# 3Dheater2.net
KiCad netlist of a schematic drawn in Altium Designer
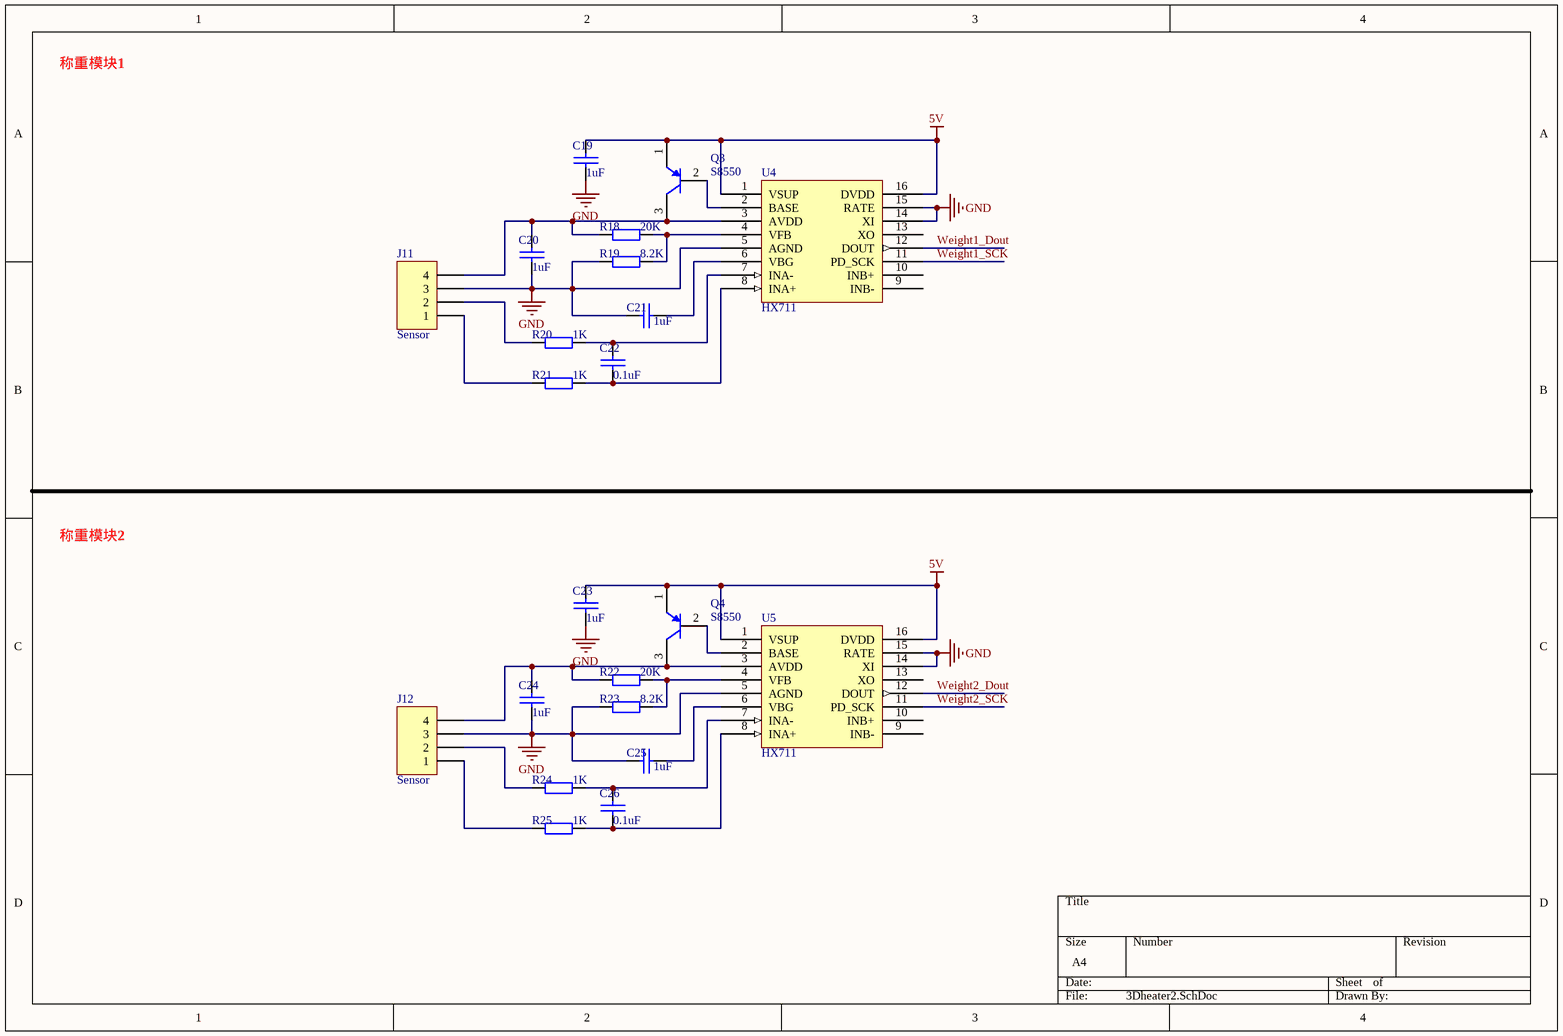
[diagram p0: 3Dheater2.SchDoc]

(export (version "E")
  (design (tool "Eeschema 10.0.6"))
  (components
    (comp (ref "C19")
      (value "1uF")
      (footprint "C0805")
      (description "Capacitor")
      (libsource (lib "Miscellaneous Devices") (part "CAP"))
    )
    (comp (ref "C20")
      (value "1uF")
      (footprint "C0805")
      (description "Capacitor")
      (libsource (lib "Miscellaneous Devices") (part "CAP"))
    )
    (comp (ref "C21")
      (value "1uF")
      (footprint "C0805")
      (description "Capacitor")
      (libsource (lib "Miscellaneous Devices") (part "CAP"))
    )
    (comp (ref "C22")
      (value "0.1uF")
      (footprint "C0805")
      (description "Capacitor")
      (libsource (lib "Miscellaneous Devices") (part "CAP"))
    )
    (comp (ref "C23")
      (value "1uF")
      (footprint "C0805")
      (description "Capacitor")
      (libsource (lib "Miscellaneous Devices") (part "CAP"))
    )
    (comp (ref "C24")
      (value "1uF")
      (footprint "C0805")
      (description "Capacitor")
      (libsource (lib "Miscellaneous Devices") (part "CAP"))
    )
    (comp (ref "C25")
      (value "1uF")
      (footprint "C0805")
      (description "Capacitor")
      (libsource (lib "Miscellaneous Devices") (part "CAP"))
    )
    (comp (ref "C26")
      (value "0.1uF")
      (footprint "C0805")
      (description "Capacitor")
      (libsource (lib "Miscellaneous Devices") (part "CAP"))
    )
    (comp (ref "J11")
      (value "Sensor")
      (footprint "HDR1X4")
      (description "Header, 4-Pin")
      (fields (field (name "PUBLISHER") "Altium Limited"))
      (libsource (lib "liuxiaolong") (part "Header 4"))
    )
    (comp (ref "J12")
      (value "Sensor")
      (footprint "HDR1X4")
      (description "Header, 4-Pin")
      (fields (field (name "PUBLISHER") "Altium Limited"))
      (libsource (lib "liuxiaolong") (part "Header 4"))
    )
    (comp (ref "Q3")
      (value "S8550")
      (footprint "SOT-23-3L")
      (description "PNP三极管")
      (fields (field (name "PUBLISHER") "Altium Limited"))
      (libsource (lib "fszhang") (part "S8550"))
    )
    (comp (ref "Q4")
      (value "S8550")
      (footprint "SOT-23-3L")
      (description "PNP三极管")
      (fields (field (name "PUBLISHER") "Altium Limited"))
      (libsource (lib "fszhang") (part "S8550"))
    )
    (comp (ref "R18")
      (value "20K")
      (footprint "R0805")
      (description "贴片电阻")
      (fields (field (name "PUBLISHER") "Altium Limited"))
      (libsource (lib "fszhang") (part "Res1"))
    )
    (comp (ref "R19")
      (value "8.2K")
      (footprint "R0805")
      (description "贴片电阻")
      (fields (field (name "PUBLISHER") "Altium Limited"))
      (libsource (lib "fszhang") (part "Res1"))
    )
    (comp (ref "R20")
      (value "1K")
      (footprint "R0805")
      (description "贴片电阻")
      (fields (field (name "PUBLISHER") "Altium Limited"))
      (libsource (lib "fszhang") (part "Res1"))
    )
    (comp (ref "R21")
      (value "1K")
      (footprint "R0805")
      (description "贴片电阻")
      (fields (field (name "PUBLISHER") "Altium Limited"))
      (libsource (lib "fszhang") (part "Res1"))
    )
    (comp (ref "R22")
      (value "20K")
      (footprint "R0805")
      (description "贴片电阻")
      (fields (field (name "PUBLISHER") "Altium Limited"))
      (libsource (lib "fszhang") (part "Res1"))
    )
    (comp (ref "R23")
      (value "8.2K")
      (footprint "R0805")
      (description "贴片电阻")
      (fields (field (name "PUBLISHER") "Altium Limited"))
      (libsource (lib "fszhang") (part "Res1"))
    )
    (comp (ref "R24")
      (value "1K")
      (footprint "R0805")
      (description "贴片电阻")
      (fields (field (name "PUBLISHER") "Altium Limited"))
      (libsource (lib "fszhang") (part "Res1"))
    )
    (comp (ref "R25")
      (value "1K")
      (footprint "R0805")
      (description "贴片电阻")
      (fields (field (name "PUBLISHER") "Altium Limited"))
      (libsource (lib "fszhang") (part "Res1"))
    )
    (comp (ref "U4")
      (value "HX711")
      (footprint "SOP16M")
      (description "AD转换")
      (libsource (lib "liuxiaolong") (part "HX711"))
    )
    (comp (ref "U5")
      (value "HX711")
      (footprint "SOP16M")
      (description "AD转换")
      (libsource (lib "liuxiaolong") (part "HX711"))
    )
  )
  (nets
    (net (code "1") (name "/Weight1_Dout") (class "Default")
      (node (ref "U4") (pin "12") (pinfunction "DOUT_12") (pintype "output"))
    )
    (net (code "2") (name "/Weight1_SCK") (class "Default")
      (node (ref "U4") (pin "11") (pinfunction "PD_SCK_11") (pintype "passive"))
    )
    (net (code "3") (name "/Weight2_Dout") (class "Default")
      (node (ref "U5") (pin "12") (pinfunction "DOUT_12") (pintype "output"))
    )
    (net (code "4") (name "/Weight2_SCK") (class "Default")
      (node (ref "U5") (pin "11") (pinfunction "PD_SCK_11") (pintype "passive"))
    )
    (net (code "5") (name "5V") (class "Default")
      (node (ref "C19") (pin "1") (pinfunction "1_1") (pintype "passive"))
      (node (ref "C23") (pin "1") (pinfunction "1_1") (pintype "passive"))
      (node (ref "Q3") (pin "1") (pinfunction "E_1") (pintype "passive"))
      (node (ref "Q4") (pin "1") (pinfunction "E_1") (pintype "passive"))
      (node (ref "U4") (pin "1") (pinfunction "VSUP_1") (pintype "passive"))
      (node (ref "U4") (pin "16") (pinfunction "DVDD_16") (pintype "power_in"))
      (node (ref "U5") (pin "1") (pinfunction "VSUP_1") (pintype "passive"))
      (node (ref "U5") (pin "16") (pinfunction "DVDD_16") (pintype "power_in"))
    )
    (net (code "6") (name "GND") (class "Default")
      (node (ref "C19") (pin "2") (pinfunction "2_2") (pintype "passive"))
      (node (ref "C20") (pin "1") (pinfunction "1_1") (pintype "passive"))
      (node (ref "C21") (pin "2") (pinfunction "2_2") (pintype "passive"))
      (node (ref "C23") (pin "2") (pinfunction "2_2") (pintype "passive"))
      (node (ref "C24") (pin "1") (pinfunction "1_1") (pintype "passive"))
      (node (ref "C25") (pin "2") (pinfunction "2_2") (pintype "passive"))
      (node (ref "J11") (pin "3") (pinfunction "3_3") (pintype "passive"))
      (node (ref "J12") (pin "3") (pinfunction "3_3") (pintype "passive"))
      (node (ref "R19") (pin "2") (pinfunction "2_2") (pintype "passive"))
      (node (ref "R23") (pin "2") (pinfunction "2_2") (pintype "passive"))
      (node (ref "U4") (pin "14") (pinfunction "XI_14") (pintype "passive"))
      (node (ref "U4") (pin "15") (pinfunction "RATE_15") (pintype "passive"))
      (node (ref "U4") (pin "5") (pinfunction "AGND_5") (pintype "passive"))
      (node (ref "U5") (pin "14") (pinfunction "XI_14") (pintype "passive"))
      (node (ref "U5") (pin "15") (pinfunction "RATE_15") (pintype "passive"))
      (node (ref "U5") (pin "5") (pinfunction "AGND_5") (pintype "passive"))
    )
    (net (code "7") (name "Net-(J11-Pad1)") (class "Default")
      (node (ref "J11") (pin "1") (pinfunction "1_1") (pintype "passive"))
      (node (ref "R21") (pin "2") (pinfunction "2_2") (pintype "passive"))
    )
    (net (code "8") (name "Net-(J11-Pad2)") (class "Default")
      (node (ref "J11") (pin "2") (pinfunction "2_2") (pintype "passive"))
      (node (ref "R20") (pin "2") (pinfunction "2_2") (pintype "passive"))
    )
    (net (code "9") (name "Net-(J12-Pad1)") (class "Default")
      (node (ref "J12") (pin "1") (pinfunction "1_1") (pintype "passive"))
      (node (ref "R25") (pin "2") (pinfunction "2_2") (pintype "passive"))
    )
    (net (code "10") (name "Net-(J12-Pad2)") (class "Default")
      (node (ref "J12") (pin "2") (pinfunction "2_2") (pintype "passive"))
      (node (ref "R24") (pin "2") (pinfunction "2_2") (pintype "passive"))
    )
    (net (code "11") (name "Net-(Q3-B)") (class "Default")
      (node (ref "Q3") (pin "2") (pinfunction "B_2") (pintype "passive"))
      (node (ref "U4") (pin "2") (pinfunction "BASE_2") (pintype "passive"))
    )
    (net (code "12") (name "Net-(Q3-C)") (class "Default")
      (node (ref "C20") (pin "2") (pinfunction "2_2") (pintype "passive"))
      (node (ref "J11") (pin "4") (pinfunction "4_4") (pintype "passive"))
      (node (ref "Q3") (pin "3") (pinfunction "C_3") (pintype "passive"))
      (node (ref "R18") (pin "2") (pinfunction "2_2") (pintype "passive"))
      (node (ref "U4") (pin "3") (pinfunction "AVDD_3") (pintype "passive"))
    )
    (net (code "13") (name "Net-(Q4-B)") (class "Default")
      (node (ref "Q4") (pin "2") (pinfunction "B_2") (pintype "passive"))
      (node (ref "U5") (pin "2") (pinfunction "BASE_2") (pintype "passive"))
    )
    (net (code "14") (name "Net-(Q4-C)") (class "Default")
      (node (ref "C24") (pin "2") (pinfunction "2_2") (pintype "passive"))
      (node (ref "J12") (pin "4") (pinfunction "4_4") (pintype "passive"))
      (node (ref "Q4") (pin "3") (pinfunction "C_3") (pintype "passive"))
      (node (ref "R22") (pin "2") (pinfunction "2_2") (pintype "passive"))
      (node (ref "U5") (pin "3") (pinfunction "AVDD_3") (pintype "passive"))
    )
    (net (code "15") (name "Net-(U4-INA+)") (class "Default")
      (node (ref "C22") (pin "1") (pinfunction "1_1") (pintype "passive"))
      (node (ref "R21") (pin "1") (pinfunction "1_1") (pintype "passive"))
      (node (ref "U4") (pin "8") (pinfunction "INA+_8") (pintype "input"))
    )
    (net (code "16") (name "Net-(U4-INA-)") (class "Default")
      (node (ref "C22") (pin "2") (pinfunction "2_2") (pintype "passive"))
      (node (ref "R20") (pin "1") (pinfunction "1_1") (pintype "passive"))
      (node (ref "U4") (pin "7") (pinfunction "INA-_7") (pintype "input"))
    )
    (net (code "17") (name "Net-(U4-VBG)") (class "Default")
      (node (ref "C21") (pin "1") (pinfunction "1_1") (pintype "passive"))
      (node (ref "U4") (pin "6") (pinfunction "VBG_6") (pintype "passive"))
    )
    (net (code "18") (name "Net-(U4-VFB)") (class "Default")
      (node (ref "R18") (pin "1") (pinfunction "1_1") (pintype "passive"))
      (node (ref "R19") (pin "1") (pinfunction "1_1") (pintype "passive"))
      (node (ref "U4") (pin "4") (pinfunction "VFB_4") (pintype "passive"))
    )
    (net (code "19") (name "Net-(U5-INA+)") (class "Default")
      (node (ref "C26") (pin "1") (pinfunction "1_1") (pintype "passive"))
      (node (ref "R25") (pin "1") (pinfunction "1_1") (pintype "passive"))
      (node (ref "U5") (pin "8") (pinfunction "INA+_8") (pintype "input"))
    )
    (net (code "20") (name "Net-(U5-INA-)") (class "Default")
      (node (ref "C26") (pin "2") (pinfunction "2_2") (pintype "passive"))
      (node (ref "R24") (pin "1") (pinfunction "1_1") (pintype "passive"))
      (node (ref "U5") (pin "7") (pinfunction "INA-_7") (pintype "input"))
    )
    (net (code "21") (name "Net-(U5-VBG)") (class "Default")
      (node (ref "C25") (pin "1") (pinfunction "1_1") (pintype "passive"))
      (node (ref "U5") (pin "6") (pinfunction "VBG_6") (pintype "passive"))
    )
    (net (code "22") (name "Net-(U5-VFB)") (class "Default")
      (node (ref "R22") (pin "1") (pinfunction "1_1") (pintype "passive"))
      (node (ref "R23") (pin "1") (pinfunction "1_1") (pintype "passive"))
      (node (ref "U5") (pin "4") (pinfunction "VFB_4") (pintype "passive"))
    )
    (net (code "23") (name "unconnected-(U4-INB+-Pad10)") (class "Default")
      (node (ref "U4") (pin "10") (pinfunction "INB+_10") (pintype "passive"))
    )
    (net (code "24") (name "unconnected-(U4-INB--Pad9)") (class "Default")
      (node (ref "U4") (pin "9") (pinfunction "INB-_9") (pintype "passive"))
    )
    (net (code "25") (name "unconnected-(U4-XO-Pad13)") (class "Default")
      (node (ref "U4") (pin "13") (pinfunction "XO_13") (pintype "passive"))
    )
    (net (code "26") (name "unconnected-(U5-INB+-Pad10)") (class "Default")
      (node (ref "U5") (pin "10") (pinfunction "INB+_10") (pintype "passive"))
    )
    (net (code "27") (name "unconnected-(U5-INB--Pad9)") (class "Default")
      (node (ref "U5") (pin "9") (pinfunction "INB-_9") (pintype "passive"))
    )
    (net (code "28") (name "unconnected-(U5-XO-Pad13)") (class "Default")
      (node (ref "U5") (pin "13") (pinfunction "XO_13") (pintype "passive"))
    )
  )
)
